# WLAN_BLUETOOTH.net
KiCad netlist of a schematic drawn in Altium Designer
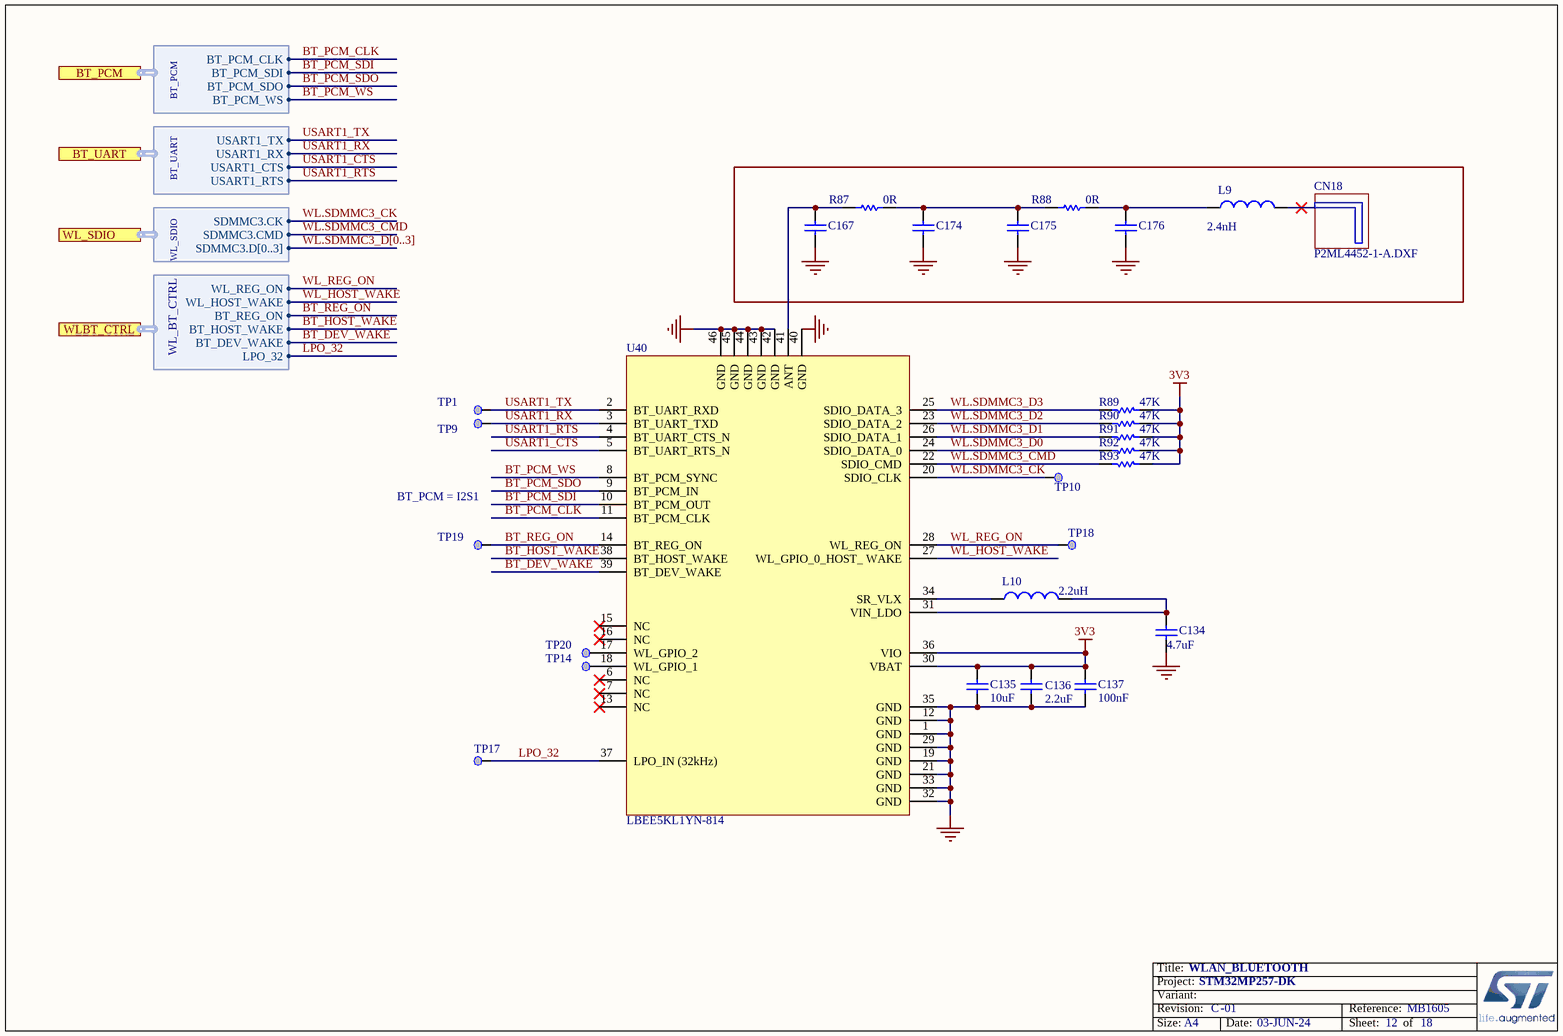
[diagram p0: WLAN_BLUETOOTH.SchDoc]

(export (version "E")
  (design (tool "Eeschema 10.0.6"))
  (components
    (comp (ref "C134")
      (value "4.7uF")
      (footprint "C0402")
      (description "Capacitor, MLCC, 4.7uF, 6V3, X5R, 20%, 0402, T=0,5mm")
      (fields
        (field (name "INTERNAL_PART_NUMBER") "MCD-01356")
        (field (name "MANUFACTURER_PART_NUMBER") "GRM155R60J475ME47")
        (field (name "PROVIDED_BY") "SUBCO")
      )
      (libsource (lib "MCD_PARTS_database") (part "Capacitor"))
    )
    (comp (ref "C135")
      (value "10uF")
      (footprint "C0603")
      (description "Capacitor, MLCC, 10uF, 10V, X5R, 10%, 0603, T=0,8mm")
      (fields
        (field (name "INTERNAL_PART_NUMBER") "MCD-00099")
        (field (name "MANUFACTURER_PART_NUMBER") "GRM188R61A106KE69D")
        (field (name "PROVIDED_BY") "SUBCO")
      )
      (libsource (lib "MCD_PARTS_database") (part "Capacitor"))
    )
    (comp (ref "C136")
      (value "2.2uF")
      (footprint "C0603")
      (description "Capacitor, MLCC, 2.2uF, 10V, X5R, 10%, 0603, T=0,8mm")
      (fields
        (field (name "INTERNAL_PART_NUMBER") "MCD-00012")
        (field (name "MANUFACTURER_PART_NUMBER") "CC0603KRX5R6BB225")
        (field (name "PROVIDED_BY") "SUBCO")
      )
      (libsource (lib "MCD_PARTS_database") (part "Capacitor"))
    )
    (comp (ref "C137")
      (value "100nF")
      (footprint "C0402")
      (description "Capacitor,100nF,16V,X7R,10%,0402")
      (fields
        (field (name "INTERNAL_PART_NUMBER") "MCD-00006")
        (field (name "MANUFACTURER_PART_NUMBER") "CC0402KRX7R7BB104")
        (field (name "PROVIDED_BY") "SUBCO")
      )
      (libsource (lib "MCD_PARTS_database") (part "Capacitor"))
    )
    (comp (ref "C167")
      (value "Capacitor")
      (footprint "C0402")
      (description "Capacitor, MLCC, 12pF, 50V, NPO, 5%, 0402, T=0,5mm")
      (fields
        (field (name "INTERNAL_PART_NUMBER") "MCD-00200")
        (field (name "MANUFACTURER_PART_NUMBER") "CC0402JRNPO9BN120")
        (field (name "PROVIDED_BY") "SUBCO")
      )
      (libsource (lib "MCD_PARTS_database") (part "Capacitor"))
    )
    (comp (ref "C174")
      (value "Capacitor")
      (footprint "C0402")
      (description "Capacitor, MLCC, 12pF, 50V, NPO, 5%, 0402, T=0,5mm")
      (fields
        (field (name "INTERNAL_PART_NUMBER") "MCD-00200")
        (field (name "MANUFACTURER_PART_NUMBER") "CC0402JRNPO9BN120")
        (field (name "PROVIDED_BY") "SUBCO")
      )
      (libsource (lib "MCD_PARTS_database") (part "Capacitor"))
    )
    (comp (ref "C175")
      (value "Capacitor")
      (footprint "C0402")
      (description "Capacitor, MLCC, 12pF, 50V, NPO, 5%, 0402, T=0,5mm")
      (fields
        (field (name "INTERNAL_PART_NUMBER") "MCD-00200")
        (field (name "MANUFACTURER_PART_NUMBER") "CC0402JRNPO9BN120")
        (field (name "PROVIDED_BY") "SUBCO")
      )
      (libsource (lib "MCD_PARTS_database") (part "Capacitor"))
    )
    (comp (ref "C176")
      (value "Capacitor")
      (footprint "C0402")
      (description "Capacitor, MLCC, 12pF, 50V, NPO, 5%, 0402, T=0,5mm")
      (fields
        (field (name "INTERNAL_PART_NUMBER") "MCD-00200")
        (field (name "MANUFACTURER_PART_NUMBER") "CC0402JRNPO9BN120")
        (field (name "PROVIDED_BY") "SUBCO")
      )
      (libsource (lib "MCD_PARTS_database") (part "Capacitor"))
    )
    (comp (ref "CN18")
      (value "P2ML4452-1-A.DXF")
      (footprint "ANT_MURATA_TYPE-1-DX_P2ML4452-1-A_DXF")
      (description "Murata_Type1DX_AntennaDesign_P2ML4452-1-A.DXF")
      (fields
        (field (name "INTERNAL_PART_NUMBER") "MCD-00656")
        (field (name "MANUFACTURER_PART_NUMBER") "Antenna design")
      )
      (libsource (lib "MCD_PARTS_database") (part "antenna_Wifi_BLE_Murata"))
    )
    (comp (ref "L9")
      (value "2.4nH")
      (footprint "IND_0402_MURATA_LQW15AN2N4C00X")
      (description "Inductor,2.4nH,+-0.2nH,0.05R,0.85A,0402")
      (fields
        (field (name "INTERNAL_PART_NUMBER") "MCD-00657")
        (field (name "MANUFACTURER_PART_NUMBER") "LQW15AN2N4C00#")
        (field (name "PROVIDED_BY") "SUBCO")
      )
      (libsource (lib "MCD_PARTS_database") (part "Inductor"))
    )
    (comp (ref "L10")
      (value "2.2uH")
      (footprint "L0603")
      (description "Inductor, 2.2µH, 20%, Isat 0.35A, DCR 0.2Ohm, 0603")
      (fields
        (field (name "INTERNAL_PART_NUMBER") "MCD-00659")
        (field (name "MANUFACTURER_PART_NUMBER") "LQM18PN2R2MGH")
        (field (name "PROVIDED_BY") "SUBCO")
      )
      (libsource (lib "MCD_PARTS_database") (part "Inductor"))
    )
    (comp (ref "R87")
      (value "0R")
      (footprint "R0402")
      (description "Resistor,0R,0402,5%,1/16W")
      (fields
        (field (name "INTERNAL_PART_NUMBER") "MCD-00052")
        (field (name "MANUFACTURER_PART_NUMBER") "RC0402JR-070RL")
        (field (name "PROVIDED_BY") "SUBCO")
      )
      (libsource (lib "MCD_PARTS_database") (part "Resistor"))
    )
    (comp (ref "R88")
      (value "0R")
      (footprint "R0402")
      (description "Resistor,0R,0402,5%,1/16W")
      (fields
        (field (name "INTERNAL_PART_NUMBER") "MCD-00052")
        (field (name "MANUFACTURER_PART_NUMBER") "RC0402JR-070RL")
        (field (name "PROVIDED_BY") "SUBCO")
      )
      (libsource (lib "MCD_PARTS_database") (part "Resistor"))
    )
    (comp (ref "R89")
      (value "47K")
      (footprint "R0402")
      (description "Resistor,47K,0402,1%,1/16W")
      (fields
        (field (name "INTERNAL_PART_NUMBER") "MCD-00063")
        (field (name "MANUFACTURER_PART_NUMBER") "RC0402FR-0747KL")
        (field (name "PROVIDED_BY") "SUBCO")
      )
      (libsource (lib "MCD_PARTS_database") (part "Resistor"))
    )
    (comp (ref "R90")
      (value "47K")
      (footprint "R0402")
      (description "Resistor,47K,0402,1%,1/16W")
      (fields
        (field (name "INTERNAL_PART_NUMBER") "MCD-00063")
        (field (name "MANUFACTURER_PART_NUMBER") "RC0402FR-0747KL")
        (field (name "PROVIDED_BY") "SUBCO")
      )
      (libsource (lib "MCD_PARTS_database") (part "Resistor"))
    )
    (comp (ref "R91")
      (value "47K")
      (footprint "R0402")
      (description "Resistor,47K,0402,1%,1/16W")
      (fields
        (field (name "INTERNAL_PART_NUMBER") "MCD-00063")
        (field (name "MANUFACTURER_PART_NUMBER") "RC0402FR-0747KL")
        (field (name "PROVIDED_BY") "SUBCO")
      )
      (libsource (lib "MCD_PARTS_database") (part "Resistor"))
    )
    (comp (ref "R92")
      (value "47K")
      (footprint "R0402")
      (description "Resistor,47K,0402,1%,1/16W")
      (fields
        (field (name "INTERNAL_PART_NUMBER") "MCD-00063")
        (field (name "MANUFACTURER_PART_NUMBER") "RC0402FR-0747KL")
        (field (name "PROVIDED_BY") "SUBCO")
      )
      (libsource (lib "MCD_PARTS_database") (part "Resistor"))
    )
    (comp (ref "R93")
      (value "47K")
      (footprint "R0402")
      (description "Resistor,47K,0402,1%,1/16W")
      (fields
        (field (name "INTERNAL_PART_NUMBER") "MCD-00063")
        (field (name "MANUFACTURER_PART_NUMBER") "RC0402FR-0747KL")
        (field (name "PROVIDED_BY") "SUBCO")
      )
      (libsource (lib "MCD_PARTS_database") (part "Resistor"))
    )
    (comp (ref "TP1")
      (value "Test Point")
      (footprint "TP_SMD_0-6MM")
      (description "Test Point 0.6mm")
      (fields (field (name "INTERNAL_PART_NUMBER") "MCD-00631"))
      (libsource (lib "MCD_PARTS_database") (part "Test Point"))
    )
    (comp (ref "TP9")
      (value "Test Point")
      (footprint "TP_SMD_0-6MM")
      (description "Test Point 0.6mm")
      (fields (field (name "INTERNAL_PART_NUMBER") "MCD-00631"))
      (libsource (lib "MCD_PARTS_database") (part "Test Point"))
    )
    (comp (ref "TP10")
      (value "Test Point")
      (footprint "TP_SMD_0-6MM")
      (description "Test Point 0.6mm")
      (fields (field (name "INTERNAL_PART_NUMBER") "MCD-00631"))
      (libsource (lib "") (part "Test Point_1"))
    )
    (comp (ref "TP14")
      (value "Test Point")
      (footprint "TP_SMD_0-6MM")
      (description "Test Point 0.6mm")
      (fields (field (name "INTERNAL_PART_NUMBER") "MCD-00631"))
      (libsource (lib "MCD_PARTS_database") (part "Test Point"))
    )
    (comp (ref "TP17")
      (value "Test Point")
      (footprint "TP_SMD_0-6MM")
      (description "Test Point 0.6mm")
      (fields (field (name "INTERNAL_PART_NUMBER") "MCD-00631"))
      (libsource (lib "MCD_PARTS_database") (part "Test Point"))
    )
    (comp (ref "TP18")
      (value "Test Point")
      (footprint "TP_SMD_0-6MM")
      (description "Test Point 0.6mm")
      (fields (field (name "INTERNAL_PART_NUMBER") "MCD-00631"))
      (libsource (lib "") (part "Test Point_1"))
    )
    (comp (ref "TP19")
      (value "Test Point")
      (footprint "TP_SMD_0-6MM")
      (description "Test Point 0.6mm")
      (fields (field (name "INTERNAL_PART_NUMBER") "MCD-00631"))
      (libsource (lib "MCD_PARTS_database") (part "Test Point"))
    )
    (comp (ref "TP20")
      (value "Test Point")
      (footprint "TP_SMD_0-6MM")
      (description "Test Point 0.6mm")
      (fields (field (name "INTERNAL_PART_NUMBER") "MCD-00631"))
      (libsource (lib "MCD_PARTS_database") (part "Test Point"))
    )
    (comp (ref "U40")
      (value "LBEE5KL1YN-814")
      (footprint "MOD_WLAN-BT_MURATA_LBEE5KL1YN-814")
      (description "IC, IEEE802.11b/g/n W-LAN + Bluetooth 5.2(BR/EDR/BLE) module")
      (fields (field (name "INTERNAL_PART_NUMBER") "MCD-03465") (field (name "MANUFACTURER") "MURATA"))
      (libsource (lib "MCD_PARTS_database") (part "LBEE5KL1YN-814"))
    )
  )
  (nets
    (net (code "5") (name "/BT_DEV_WAKE") (class "Default")
      (node (ref "U40") (pin "39") (pinfunction "BT_DEV_WAKE_39") (pintype "passive"))
    )
    (net (code "6") (name "/BT_HOST_WAKE") (class "Default")
      (node (ref "U40") (pin "38") (pinfunction "BT_HOST_WAKE_38") (pintype "passive"))
    )
    (net (code "7") (name "/BT_PCM_CLK") (class "Default")
      (node (ref "U40") (pin "11") (pinfunction "BT_PCM_CLK_11") (pintype "passive"))
    )
    (net (code "8") (name "/BT_PCM_SDI") (class "Default")
      (node (ref "U40") (pin "10") (pinfunction "BT_PCM_OUT_10") (pintype "passive"))
    )
    (net (code "9") (name "/BT_PCM_SDO") (class "Default")
      (node (ref "U40") (pin "9") (pinfunction "BT_PCM_IN_9") (pintype "passive"))
    )
    (net (code "10") (name "/BT_PCM_WS") (class "Default")
      (node (ref "U40") (pin "8") (pinfunction "BT_PCM_SYNC_8") (pintype "passive"))
    )
    (net (code "11") (name "/BT_REG_ON") (class "Default")
      (node (ref "TP19") (pin "1") (pinfunction "1_1") (pintype "passive"))
      (node (ref "U40") (pin "14") (pinfunction "BT_REG_ON_14") (pintype "passive"))
    )
    (net (code "12") (name "/LPO_32") (class "Default")
      (node (ref "TP17") (pin "1") (pinfunction "1_1") (pintype "passive"))
      (node (ref "U40") (pin "37") (pinfunction "LPO_IN_(32kHz)_37") (pintype "passive"))
    )
    (net (code "13") (name "/USART1_CTS") (class "Default")
      (node (ref "U40") (pin "5") (pinfunction "BT_UART_RTS_N_5") (pintype "passive"))
    )
    (net (code "14") (name "/USART1_RTS") (class "Default")
      (node (ref "U40") (pin "4") (pinfunction "BT_UART_CTS_N_4") (pintype "passive"))
    )
    (net (code "15") (name "/USART1_RX") (class "Default")
      (node (ref "TP9") (pin "1") (pinfunction "1_1") (pintype "passive"))
      (node (ref "U40") (pin "3") (pinfunction "BT_UART_TXD_3") (pintype "passive"))
    )
    (net (code "16") (name "/USART1_TX") (class "Default")
      (node (ref "TP1") (pin "1") (pinfunction "1_1") (pintype "passive"))
      (node (ref "U40") (pin "2") (pinfunction "BT_UART_RXD_2") (pintype "passive"))
    )
    (net (code "17") (name "/WL.SDMMC3_CK") (class "Default")
      (node (ref "TP10") (pin "1") (pinfunction "1_1") (pintype "passive"))
      (node (ref "U40") (pin "20") (pinfunction "SDIO_CLK_20") (pintype "passive"))
    )
    (net (code "18") (name "/WL.SDMMC3_CMD") (class "Default")
      (node (ref "R93") (pin "2") (pinfunction "2_2") (pintype "passive"))
      (node (ref "U40") (pin "22") (pinfunction "SDIO_CMD_22") (pintype "passive"))
    )
    (net (code "19") (name "/WL.SDMMC3_D0") (class "Default")
      (node (ref "R92") (pin "2") (pinfunction "2_2") (pintype "passive"))
      (node (ref "U40") (pin "24") (pinfunction "SDIO_DATA_0_24") (pintype "passive"))
    )
    (net (code "20") (name "/WL.SDMMC3_D1") (class "Default")
      (node (ref "R91") (pin "2") (pinfunction "2_2") (pintype "passive"))
      (node (ref "U40") (pin "26") (pinfunction "SDIO_DATA_1_26") (pintype "passive"))
    )
    (net (code "21") (name "/WL.SDMMC3_D2") (class "Default")
      (node (ref "R90") (pin "2") (pinfunction "2_2") (pintype "passive"))
      (node (ref "U40") (pin "23") (pinfunction "SDIO_DATA_2_23") (pintype "passive"))
    )
    (net (code "22") (name "/WL.SDMMC3_D3") (class "Default")
      (node (ref "R89") (pin "2") (pinfunction "2_2") (pintype "passive"))
      (node (ref "U40") (pin "25") (pinfunction "SDIO_DATA_3_25") (pintype "passive"))
    )
    (net (code "23") (name "/WL_HOST_WAKE") (class "Default")
      (node (ref "U40") (pin "27") (pinfunction "WL_GPIO_0_HOST__WAKE_27") (pintype "passive"))
    )
    (net (code "24") (name "/WL_REG_ON") (class "Default")
      (node (ref "TP18") (pin "1") (pinfunction "1_1") (pintype "passive"))
      (node (ref "U40") (pin "28") (pinfunction "WL_REG_ON_28") (pintype "passive"))
    )
    (net (code "30") (name "3V3") (class "Default")
      (node (ref "C135") (pin "2") (pinfunction "2_2") (pintype "passive"))
      (node (ref "C136") (pin "2") (pinfunction "2_2") (pintype "passive"))
      (node (ref "C137") (pin "2") (pinfunction "2_2") (pintype "passive"))
      (node (ref "R89") (pin "1") (pinfunction "1_1") (pintype "passive"))
      (node (ref "R90") (pin "1") (pinfunction "1_1") (pintype "passive"))
      (node (ref "R91") (pin "1") (pinfunction "1_1") (pintype "passive"))
      (node (ref "R92") (pin "1") (pinfunction "1_1") (pintype "passive"))
      (node (ref "R93") (pin "1") (pinfunction "1_1") (pintype "passive"))
      (node (ref "U40") (pin "30") (pinfunction "VBAT_30") (pintype "passive"))
      (node (ref "U40") (pin "36") (pinfunction "VIO_36") (pintype "passive"))
    )
    (net (code "31") (name "GND") (class "Default")
      (node (ref "C134") (pin "1") (pinfunction "1_1") (pintype "passive"))
      (node (ref "C135") (pin "1") (pinfunction "1_1") (pintype "passive"))
      (node (ref "C136") (pin "1") (pinfunction "1_1") (pintype "passive"))
      (node (ref "C137") (pin "1") (pinfunction "1_1") (pintype "passive"))
      (node (ref "C167") (pin "1") (pinfunction "1_1") (pintype "passive"))
      (node (ref "C174") (pin "1") (pinfunction "1_1") (pintype "passive"))
      (node (ref "C175") (pin "1") (pinfunction "1_1") (pintype "passive"))
      (node (ref "C176") (pin "1") (pinfunction "1_1") (pintype "passive"))
      (node (ref "U40") (pin "1") (pinfunction "GND_1") (pintype "passive"))
      (node (ref "U40") (pin "12") (pinfunction "GND_12") (pintype "passive"))
      (node (ref "U40") (pin "19") (pinfunction "GND_19") (pintype "passive"))
      (node (ref "U40") (pin "21") (pinfunction "GND_21") (pintype "passive"))
      (node (ref "U40") (pin "29") (pinfunction "GND_29") (pintype "passive"))
      (node (ref "U40") (pin "32") (pinfunction "GND_32") (pintype "passive"))
      (node (ref "U40") (pin "33") (pinfunction "GND_33") (pintype "passive"))
      (node (ref "U40") (pin "35") (pinfunction "GND_35") (pintype "passive"))
      (node (ref "U40") (pin "40") (pinfunction "GND_40") (pintype "passive"))
      (node (ref "U40") (pin "42") (pinfunction "GND_42") (pintype "passive"))
      (node (ref "U40") (pin "43") (pinfunction "GND_43") (pintype "passive"))
      (node (ref "U40") (pin "44") (pinfunction "GND_44") (pintype "passive"))
      (node (ref "U40") (pin "45") (pinfunction "GND_45") (pintype "passive"))
      (node (ref "U40") (pin "46") (pinfunction "GND_46") (pintype "passive"))
    )
    (net (code "32") (name "Net-(C174-Pad2)") (class "Default")
      (node (ref "C174") (pin "2") (pinfunction "2_2") (pintype "passive"))
      (node (ref "C175") (pin "2") (pinfunction "2_2") (pintype "passive"))
      (node (ref "R87") (pin "1") (pinfunction "1_1") (pintype "passive"))
      (node (ref "R88") (pin "2") (pinfunction "2_2") (pintype "passive"))
    )
    (net (code "33") (name "Net-(C176-Pad2)") (class "Default")
      (node (ref "C176") (pin "2") (pinfunction "2_2") (pintype "passive"))
      (node (ref "L9") (pin "1") (pinfunction "1_1") (pintype "passive"))
      (node (ref "R88") (pin "1") (pinfunction "1_1") (pintype "passive"))
    )
    (net (code "34") (name "Net-(U40-ANT)") (class "Default")
      (node (ref "C167") (pin "2") (pinfunction "2_2") (pintype "passive"))
      (node (ref "R87") (pin "2") (pinfunction "2_2") (pintype "passive"))
      (node (ref "U40") (pin "41") (pinfunction "ANT_41") (pintype "passive"))
    )
    (net (code "35") (name "Net-(U40-SR_VLX)") (class "Default")
      (node (ref "L10") (pin "1") (pinfunction "1_1") (pintype "passive"))
      (node (ref "U40") (pin "34") (pinfunction "SR_VLX_34") (pintype "passive"))
    )
    (net (code "36") (name "Net-(U40-VIN_LDO)") (class "Default")
      (node (ref "C134") (pin "2") (pinfunction "2_2") (pintype "passive"))
      (node (ref "L10") (pin "2") (pinfunction "2_2") (pintype "passive"))
      (node (ref "U40") (pin "31") (pinfunction "VIN_LDO_31") (pintype "passive"))
    )
    (net (code "37") (name "Net-(U40-WL_GPIO_1)") (class "Default")
      (node (ref "TP14") (pin "1") (pinfunction "1_1") (pintype "passive"))
      (node (ref "U40") (pin "18") (pinfunction "WL_GPIO_1_18") (pintype "passive"))
    )
    (net (code "38") (name "Net-(U40-WL_GPIO_2)") (class "Default")
      (node (ref "TP20") (pin "1") (pinfunction "1_1") (pintype "passive"))
      (node (ref "U40") (pin "17") (pinfunction "WL_GPIO_2_17") (pintype "passive"))
    )
    (net (code "39") (name "unconnected-(L9-Pad2)") (class "Default")
      (node (ref "L9") (pin "2") (pinfunction "2_2") (pintype "passive"))
    )
    (net (code "40") (name "unconnected-(U40-NC-Pad6)") (class "Default")
      (node (ref "U40") (pin "6") (pinfunction "NC_6") (pintype "passive+no_connect"))
    )
    (net (code "41") (name "unconnected-(U40-NC-Pad7)") (class "Default")
      (node (ref "U40") (pin "7") (pinfunction "NC_7") (pintype "passive+no_connect"))
    )
    (net (code "42") (name "unconnected-(U40-NC-Pad13)") (class "Default")
      (node (ref "U40") (pin "13") (pinfunction "NC_13") (pintype "passive+no_connect"))
    )
    (net (code "43") (name "unconnected-(U40-NC-Pad15)") (class "Default")
      (node (ref "U40") (pin "15") (pinfunction "NC_15") (pintype "passive+no_connect"))
    )
    (net (code "44") (name "unconnected-(U40-NC-Pad16)") (class "Default")
      (node (ref "U40") (pin "16") (pinfunction "NC_16") (pintype "passive+no_connect"))
    )
  )
)
